# WiFi_board.net
KiCad netlist of a schematic drawn in Altium Designer
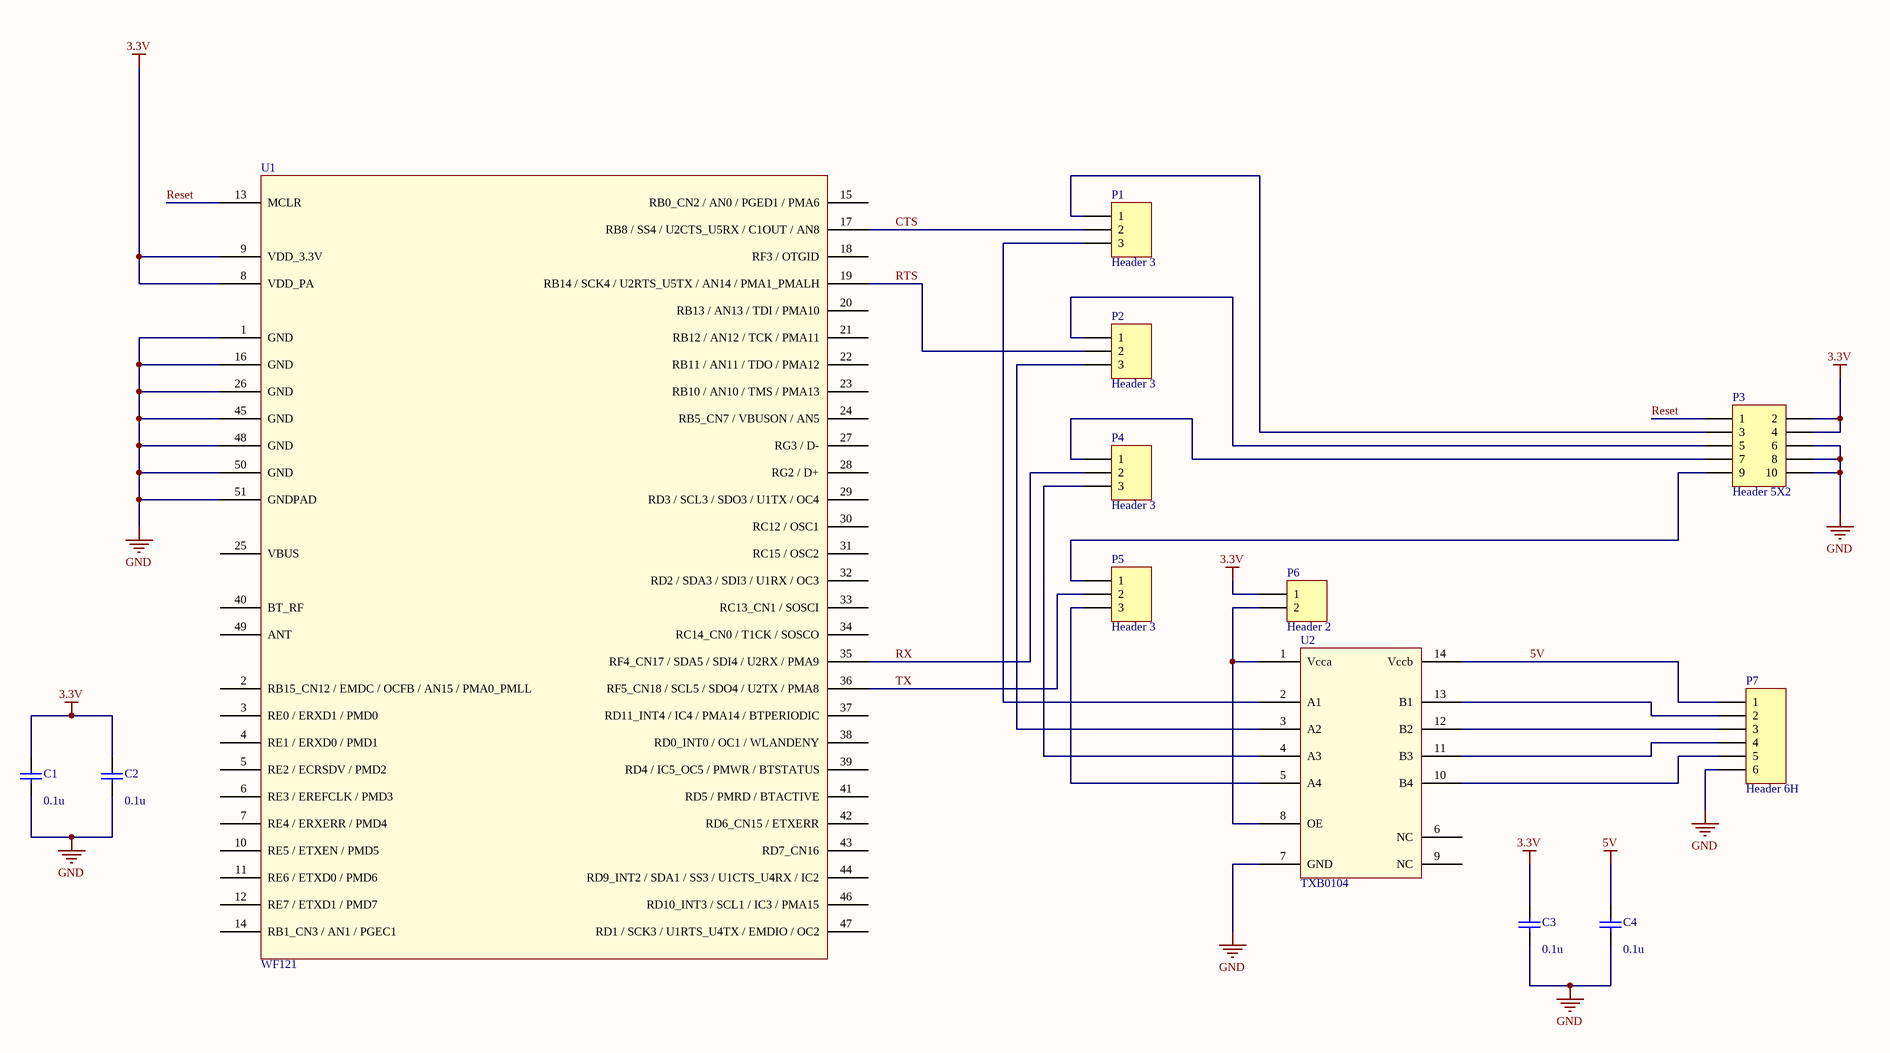
[diagram p0: WiFi_board.SchDoc]

(export (version "E")
  (design (tool "Eeschema 10.0.6"))
  (components
    (comp (ref "C1")
      (value "0.1u")
      (footprint "C1206")
      (description "Capacitor (Semiconductor SIM Model)")
      (fields (field (name "Comment") "C1") (field (name "PUBLISHER") "Altium Limited"))
      (libsource (lib "Miscellaneous Devices") (part "Cap Semi"))
    )
    (comp (ref "C2")
      (value "0.1u")
      (footprint "C1206")
      (description "Capacitor (Semiconductor SIM Model)")
      (fields (field (name "Comment") "C2") (field (name "PUBLISHER") "Altium Limited"))
      (libsource (lib "Miscellaneous Devices") (part "Cap Semi"))
    )
    (comp (ref "C3")
      (value "0.1u")
      (footprint "C1206")
      (description "Capacitor (Semiconductor SIM Model)")
      (fields (field (name "Comment") "Cap Semi") (field (name "PUBLISHER") "Altium Limited"))
      (libsource (lib "Miscellaneous Devices") (part "Cap Semi"))
    )
    (comp (ref "C4")
      (value "0.1u")
      (footprint "C1206")
      (description "Capacitor (Semiconductor SIM Model)")
      (fields (field (name "Comment") "Cap Semi") (field (name "PUBLISHER") "Altium Limited"))
      (libsource (lib "Miscellaneous Devices") (part "Cap Semi"))
    )
    (comp (ref "P1")
      (value "Header 3")
      (footprint "HDR1X3")
      (description "Header, 3-Pin")
      (fields (field (name "PUBLISHER") "Altium Limited"))
      (libsource (lib "Miscellaneous Connectors") (part "Header 3"))
    )
    (comp (ref "P2")
      (value "Header 3")
      (footprint "HDR1X3")
      (description "Header, 3-Pin")
      (fields (field (name "PUBLISHER") "Altium Limited"))
      (libsource (lib "Miscellaneous Connectors") (part "Header 3"))
    )
    (comp (ref "P3")
      (value "Header 5X2")
      (footprint "HDR2X5")
      (description "Header, 5-Pin, Dual row")
      (fields (field (name "PUBLISHER") "Altium Limited"))
      (libsource (lib "Miscellaneous Connectors") (part "Header 5X2"))
    )
    (comp (ref "P4")
      (value "Header 3")
      (footprint "HDR1X3")
      (description "Header, 3-Pin")
      (fields (field (name "PUBLISHER") "Altium Limited"))
      (libsource (lib "Miscellaneous Connectors") (part "Header 3"))
    )
    (comp (ref "P5")
      (value "Header 3")
      (footprint "HDR1X3")
      (description "Header, 3-Pin")
      (fields (field (name "PUBLISHER") "Altium Limited"))
      (libsource (lib "Miscellaneous Connectors") (part "Header 3"))
    )
    (comp (ref "P6")
      (value "Header 2")
      (footprint "HDR1X2")
      (description "Header, 2-Pin")
      (fields (field (name "PUBLISHER") "Altium Limited"))
      (libsource (lib "Miscellaneous Connectors") (part "Header 2"))
    )
    (comp (ref "P7")
      (value "Header 6H")
      (footprint "HDR1X6H")
      (description "Header, 6-Pin, Right Angle")
      (fields (field (name "PUBLISHER") "Altium Limited"))
      (libsource (lib "Miscellaneous Connectors") (part "Header 6H"))
    )
    (comp (ref "U1") (value "WF121") (footprint "WF121") (libsource (lib "QuadrupedSchLib") (part "WF121")))
    (comp (ref "U2")
      (value "TXB0104")
      (footprint "TSSOP65P640X120-14N")
      (libsource (lib "QuadrupedSchLib") (part "TXB0104"))
    )
  )
  (nets
    (net (code "1") (name "/CTS") (class "Default")
      (node (ref "P1") (pin "2") (pinfunction "2_2") (pintype "passive"))
      (node (ref "U1") (pin "17") (pinfunction "RB8_/_SS4_/_U2CTS_U5RX_/_C1OUT_/_AN8_17") (pintype "passive"))
    )
    (net (code "2") (name "/RTS") (class "Default")
      (node (ref "P2") (pin "2") (pinfunction "2_2") (pintype "passive"))
      (node (ref "U1") (pin "19") (pinfunction "RB14_/_SCK4_/_U2RTS_U5TX_/_AN14_/_PMA1_PMALH_19") (pintype "passive"))
    )
    (net (code "3") (name "/RX") (class "Default")
      (node (ref "P4") (pin "2") (pinfunction "2_2") (pintype "passive"))
      (node (ref "U1") (pin "35") (pinfunction "RF4_CN17_/_SDA5_/_SDI4_/_U2RX_/_PMA9_35") (pintype "passive"))
    )
    (net (code "4") (name "/Reset") (class "Default")
      (node (ref "P3") (pin "1") (pinfunction "1_1") (pintype "passive"))
      (node (ref "U1") (pin "13") (pinfunction "MCLR_13") (pintype "passive"))
    )
    (net (code "5") (name "/TX") (class "Default")
      (node (ref "P5") (pin "2") (pinfunction "2_2") (pintype "passive"))
      (node (ref "U1") (pin "36") (pinfunction "RF5_CN18_/_SCL5_/_SDO4_/_U2TX_/_PMA8_36") (pintype "passive"))
    )
    (net (code "6") (name "3.3V") (class "Default")
      (node (ref "C1") (pin "2") (pinfunction "2_2") (pintype "passive"))
      (node (ref "C2") (pin "2") (pinfunction "2_2") (pintype "passive"))
      (node (ref "C3") (pin "2") (pinfunction "2_2") (pintype "passive"))
      (node (ref "P3") (pin "2") (pinfunction "2_2") (pintype "passive"))
      (node (ref "P3") (pin "4") (pinfunction "4_4") (pintype "passive"))
      (node (ref "P6") (pin "1") (pinfunction "1_1") (pintype "passive"))
      (node (ref "U1") (pin "8") (pinfunction "VDD_PA_8") (pintype "power_in"))
      (node (ref "U1") (pin "9") (pinfunction "VDD_3.3V_9") (pintype "power_in"))
    )
    (net (code "7") (name "5V") (class "Default")
      (node (ref "C4") (pin "2") (pinfunction "2_2") (pintype "passive"))
      (node (ref "P7") (pin "1") (pinfunction "1_1") (pintype "passive"))
      (node (ref "U2") (pin "14") (pinfunction "Vccb_14") (pintype "passive"))
    )
    (net (code "8") (name "GND") (class "Default")
      (node (ref "C1") (pin "1") (pinfunction "1_1") (pintype "passive"))
      (node (ref "C2") (pin "1") (pinfunction "1_1") (pintype "passive"))
      (node (ref "C3") (pin "1") (pinfunction "1_1") (pintype "passive"))
      (node (ref "C4") (pin "1") (pinfunction "1_1") (pintype "passive"))
      (node (ref "P3") (pin "10") (pinfunction "10_10") (pintype "passive"))
      (node (ref "P3") (pin "6") (pinfunction "6_6") (pintype "passive"))
      (node (ref "P3") (pin "8") (pinfunction "8_8") (pintype "passive"))
      (node (ref "P7") (pin "6") (pinfunction "6_6") (pintype "passive"))
      (node (ref "U1") (pin "1") (pinfunction "GND_1") (pintype "power_in"))
      (node (ref "U1") (pin "16") (pinfunction "GND_16") (pintype "power_in"))
      (node (ref "U1") (pin "26") (pinfunction "GND_26") (pintype "power_in"))
      (node (ref "U1") (pin "45") (pinfunction "GND_45") (pintype "power_in"))
      (node (ref "U1") (pin "48") (pinfunction "GND_48") (pintype "power_in"))
      (node (ref "U1") (pin "50") (pinfunction "GND_50") (pintype "power_in"))
      (node (ref "U1") (pin "51") (pinfunction "GNDPAD_51") (pintype "power_in"))
      (node (ref "U2") (pin "7") (pinfunction "GND_7") (pintype "power_in"))
    )
    (net (code "9") (name "Net-(P1-Pad1)") (class "Default")
      (node (ref "P1") (pin "1") (pinfunction "1_1") (pintype "passive"))
      (node (ref "P3") (pin "3") (pinfunction "3_3") (pintype "passive"))
    )
    (net (code "10") (name "Net-(P2-Pad1)") (class "Default")
      (node (ref "P2") (pin "1") (pinfunction "1_1") (pintype "passive"))
      (node (ref "P3") (pin "5") (pinfunction "5_5") (pintype "passive"))
    )
    (net (code "11") (name "Net-(P3-Pad7)") (class "Default")
      (node (ref "P3") (pin "7") (pinfunction "7_7") (pintype "passive"))
      (node (ref "P4") (pin "1") (pinfunction "1_1") (pintype "passive"))
    )
    (net (code "12") (name "Net-(P3-Pad9)") (class "Default")
      (node (ref "P3") (pin "9") (pinfunction "9_9") (pintype "passive"))
      (node (ref "P5") (pin "1") (pinfunction "1_1") (pintype "passive"))
    )
    (net (code "13") (name "Net-(U2-A1)") (class "Default")
      (node (ref "P1") (pin "3") (pinfunction "3_3") (pintype "passive"))
      (node (ref "U2") (pin "2") (pinfunction "A1_2") (pintype "passive"))
    )
    (net (code "14") (name "Net-(U2-A2)") (class "Default")
      (node (ref "P2") (pin "3") (pinfunction "3_3") (pintype "passive"))
      (node (ref "U2") (pin "3") (pinfunction "A2_3") (pintype "passive"))
    )
    (net (code "15") (name "Net-(U2-A3)") (class "Default")
      (node (ref "P4") (pin "3") (pinfunction "3_3") (pintype "passive"))
      (node (ref "U2") (pin "4") (pinfunction "A3_4") (pintype "passive"))
    )
    (net (code "16") (name "Net-(U2-A4)") (class "Default")
      (node (ref "P5") (pin "3") (pinfunction "3_3") (pintype "passive"))
      (node (ref "U2") (pin "5") (pinfunction "A4_5") (pintype "passive"))
    )
    (net (code "17") (name "Net-(U2-B1)") (class "Default")
      (node (ref "P7") (pin "2") (pinfunction "2_2") (pintype "passive"))
      (node (ref "U2") (pin "13") (pinfunction "B1_13") (pintype "passive"))
    )
    (net (code "18") (name "Net-(U2-B2)") (class "Default")
      (node (ref "P7") (pin "3") (pinfunction "3_3") (pintype "passive"))
      (node (ref "U2") (pin "12") (pinfunction "B2_12") (pintype "passive"))
    )
    (net (code "19") (name "Net-(U2-B3)") (class "Default")
      (node (ref "P7") (pin "4") (pinfunction "4_4") (pintype "passive"))
      (node (ref "U2") (pin "11") (pinfunction "B3_11") (pintype "passive"))
    )
    (net (code "20") (name "Net-(U2-B4)") (class "Default")
      (node (ref "P7") (pin "5") (pinfunction "5_5") (pintype "passive"))
      (node (ref "U2") (pin "10") (pinfunction "B4_10") (pintype "passive"))
    )
    (net (code "21") (name "Net-(U2-OE)") (class "Default")
      (node (ref "P6") (pin "2") (pinfunction "2_2") (pintype "passive"))
      (node (ref "U2") (pin "1") (pinfunction "Vcca_1") (pintype "power_in"))
      (node (ref "U2") (pin "8") (pinfunction "OE_8") (pintype "passive"))
    )
    (net (code "22") (name "unconnected-(U1-ANT-Pad49)") (class "Default")
      (node (ref "U1") (pin "49") (pinfunction "ANT_49") (pintype "passive"))
    )
    (net (code "23") (name "unconnected-(U1-BT_RF-Pad40)") (class "Default")
      (node (ref "U1") (pin "40") (pinfunction "BT_RF_40") (pintype "passive"))
    )
    (net (code "24") (name "unconnected-(U1-RB0_CN2_{slash}_AN0_{slash}_PGED1_{slash}_PMA6-Pad15)") (class "Default")
      (node (ref "U1") (pin "15") (pinfunction "RB0_CN2_/_AN0_/_PGED1_/_PMA6_15") (pintype "passive"))
    )
    (net (code "25") (name "unconnected-(U1-RB1_CN3_{slash}_AN1_{slash}_PGEC1-Pad14)") (class "Default")
      (node (ref "U1") (pin "14") (pinfunction "RB1_CN3_/_AN1_/_PGEC1_14") (pintype "passive"))
    )
    (net (code "26") (name "unconnected-(U1-RB5_CN7_{slash}_VBUSON_{slash}_AN5-Pad24)") (class "Default")
      (node (ref "U1") (pin "24") (pinfunction "RB5_CN7_/_VBUSON_/_AN5_24") (pintype "passive"))
    )
    (net (code "27") (name "unconnected-(U1-RB10_{slash}_AN10_{slash}_TMS_{slash}_PMA13-Pad23)") (class "Default")
      (node (ref "U1") (pin "23") (pinfunction "RB10_/_AN10_/_TMS_/_PMA13_23") (pintype "passive"))
    )
    (net (code "28") (name "unconnected-(U1-RB11_{slash}_AN11_{slash}_TDO_{slash}_PMA12-Pad22)") (class "Default")
      (node (ref "U1") (pin "22") (pinfunction "RB11_/_AN11_/_TDO_/_PMA12_22") (pintype "passive"))
    )
    (net (code "29") (name "unconnected-(U1-RB12_{slash}_AN12_{slash}_TCK_{slash}_PMA11-Pad21)") (class "Default")
      (node (ref "U1") (pin "21") (pinfunction "RB12_/_AN12_/_TCK_/_PMA11_21") (pintype "passive"))
    )
    (net (code "30") (name "unconnected-(U1-RB13_{slash}_AN13_{slash}_TDI_{slash}_PMA10-Pad20)") (class "Default")
      (node (ref "U1") (pin "20") (pinfunction "RB13_/_AN13_/_TDI_/_PMA10_20") (pintype "passive"))
    )
    (net (code "31") (name "unconnected-(U1-RB15_CN12_{slash}_EMDC_{slash}_OCFB_{slash}_AN15_{slash}_PMA0_PMLL-Pad2)") (class "Default")
      (node (ref "U1") (pin "2") (pinfunction "RB15_CN12_/_EMDC_/_OCFB_/_AN15_/_PMA0_PMLL_2") (pintype "passive"))
    )
    (net (code "32") (name "unconnected-(U1-RC12_{slash}_OSC1-Pad30)") (class "Default")
      (node (ref "U1") (pin "30") (pinfunction "RC12_/_OSC1_30") (pintype "passive"))
    )
    (net (code "33") (name "unconnected-(U1-RC13_CN1_{slash}_SOSCI-Pad33)") (class "Default")
      (node (ref "U1") (pin "33") (pinfunction "RC13_CN1_/_SOSCI_33") (pintype "passive"))
    )
    (net (code "34") (name "unconnected-(U1-RC14_CN0_{slash}_T1CK_{slash}_SOSCO-Pad34)") (class "Default")
      (node (ref "U1") (pin "34") (pinfunction "RC14_CN0_/_T1CK_/_SOSCO_34") (pintype "passive"))
    )
    (net (code "35") (name "unconnected-(U1-RC15_{slash}_OSC2-Pad31)") (class "Default")
      (node (ref "U1") (pin "31") (pinfunction "RC15_/_OSC2_31") (pintype "passive"))
    )
    (net (code "36") (name "unconnected-(U1-RD0_INT0_{slash}_OC1_{slash}_WLANDENY-Pad38)") (class "Default")
      (node (ref "U1") (pin "38") (pinfunction "RD0_INT0_/_OC1_/_WLANDENY_38") (pintype "passive"))
    )
    (net (code "37") (name "unconnected-(U1-RD1_{slash}_SCK3_{slash}_U1RTS_U4TX_{slash}_EMDIO_{slash}_OC2-Pad47)") (class "Default")
      (node (ref "U1") (pin "47") (pinfunction "RD1_/_SCK3_/_U1RTS_U4TX_/_EMDIO_/_OC2_47") (pintype "passive"))
    )
    (net (code "38") (name "unconnected-(U1-RD2_{slash}_SDA3_{slash}_SDI3_{slash}_U1RX_{slash}_OC3-Pad32)") (class "Default")
      (node (ref "U1") (pin "32") (pinfunction "RD2_/_SDA3_/_SDI3_/_U1RX_/_OC3_32") (pintype "passive"))
    )
    (net (code "39") (name "unconnected-(U1-RD3_{slash}_SCL3_{slash}_SDO3_{slash}_U1TX_{slash}_OC4-Pad29)") (class "Default")
      (node (ref "U1") (pin "29") (pinfunction "RD3_/_SCL3_/_SDO3_/_U1TX_/_OC4_29") (pintype "passive"))
    )
    (net (code "40") (name "unconnected-(U1-RD4_{slash}_IC5_OC5_{slash}_PMWR_{slash}_BTSTATUS-Pad39)") (class "Default")
      (node (ref "U1") (pin "39") (pinfunction "RD4_/_IC5_OC5_/_PMWR_/_BTSTATUS_39") (pintype "passive"))
    )
    (net (code "41") (name "unconnected-(U1-RD5_{slash}_PMRD_{slash}_BTACTIVE-Pad41)") (class "Default")
      (node (ref "U1") (pin "41") (pinfunction "RD5_/_PMRD_/_BTACTIVE_41") (pintype "passive"))
    )
    (net (code "42") (name "unconnected-(U1-RD6_CN15_{slash}_ETXERR-Pad42)") (class "Default")
      (node (ref "U1") (pin "42") (pinfunction "RD6_CN15_/_ETXERR_42") (pintype "passive"))
    )
    (net (code "43") (name "unconnected-(U1-RD7_CN16-Pad43)") (class "Default")
      (node (ref "U1") (pin "43") (pinfunction "RD7_CN16_43") (pintype "passive"))
    )
    (net (code "44") (name "unconnected-(U1-RD9_INT2_{slash}_SDA1_{slash}_SS3_{slash}_U1CTS_U4RX_{slash}_IC2-Pad44)") (class "Default")
      (node (ref "U1") (pin "44") (pinfunction "RD9_INT2_/_SDA1_/_SS3_/_U1CTS_U4RX_/_IC2_44") (pintype "passive"))
    )
    (net (code "45") (name "unconnected-(U1-RD10_INT3_{slash}_SCL1_{slash}_IC3_{slash}_PMA15-Pad46)") (class "Default")
      (node (ref "U1") (pin "46") (pinfunction "RD10_INT3_/_SCL1_/_IC3_/_PMA15_46") (pintype "passive"))
    )
    (net (code "46") (name "unconnected-(U1-RD11_INT4_{slash}_IC4_{slash}_PMA14_{slash}_BTPERIODIC-Pad37)") (class "Default")
      (node (ref "U1") (pin "37") (pinfunction "RD11_INT4_/_IC4_/_PMA14_/_BTPERIODIC_37") (pintype "passive"))
    )
    (net (code "47") (name "unconnected-(U1-RE0_{slash}_ERXD1_{slash}_PMD0-Pad3)") (class "Default")
      (node (ref "U1") (pin "3") (pinfunction "RE0_/_ERXD1_/_PMD0_3") (pintype "passive"))
    )
    (net (code "48") (name "unconnected-(U1-RE1_{slash}_ERXD0_{slash}_PMD1-Pad4)") (class "Default")
      (node (ref "U1") (pin "4") (pinfunction "RE1_/_ERXD0_/_PMD1_4") (pintype "passive"))
    )
    (net (code "49") (name "unconnected-(U1-RE2_{slash}_ECRSDV_{slash}_PMD2-Pad5)") (class "Default")
      (node (ref "U1") (pin "5") (pinfunction "RE2_/_ECRSDV_/_PMD2_5") (pintype "passive"))
    )
    (net (code "50") (name "unconnected-(U1-RE3_{slash}_EREFCLK_{slash}_PMD3-Pad6)") (class "Default")
      (node (ref "U1") (pin "6") (pinfunction "RE3_/_EREFCLK_/_PMD3_6") (pintype "passive"))
    )
    (net (code "51") (name "unconnected-(U1-RE4_{slash}_ERXERR_{slash}_PMD4-Pad7)") (class "Default")
      (node (ref "U1") (pin "7") (pinfunction "RE4_/_ERXERR_/_PMD4_7") (pintype "passive"))
    )
    (net (code "52") (name "unconnected-(U1-RE5_{slash}_ETXEN_{slash}_PMD5-Pad10)") (class "Default")
      (node (ref "U1") (pin "10") (pinfunction "RE5_/_ETXEN_/_PMD5_10") (pintype "passive"))
    )
    (net (code "53") (name "unconnected-(U1-RE6_{slash}_ETXD0_{slash}_PMD6-Pad11)") (class "Default")
      (node (ref "U1") (pin "11") (pinfunction "RE6_/_ETXD0_/_PMD6_11") (pintype "passive"))
    )
    (net (code "54") (name "unconnected-(U1-RE7_{slash}_ETXD1_{slash}_PMD7-Pad12)") (class "Default")
      (node (ref "U1") (pin "12") (pinfunction "RE7_/_ETXD1_/_PMD7_12") (pintype "passive"))
    )
    (net (code "55") (name "unconnected-(U1-RF3_{slash}_OTGID-Pad18)") (class "Default")
      (node (ref "U1") (pin "18") (pinfunction "RF3_/_OTGID_18") (pintype "passive"))
    )
    (net (code "56") (name "unconnected-(U1-RG2_{slash}_D+-Pad28)") (class "Default")
      (node (ref "U1") (pin "28") (pinfunction "RG2_/_D+_28") (pintype "passive"))
    )
    (net (code "57") (name "unconnected-(U1-RG3_{slash}_D--Pad27)") (class "Default")
      (node (ref "U1") (pin "27") (pinfunction "RG3_/_D-_27") (pintype "passive"))
    )
    (net (code "58") (name "unconnected-(U1-VBUS-Pad25)") (class "Default")
      (node (ref "U1") (pin "25") (pinfunction "VBUS_25") (pintype "power_in"))
    )
    (net (code "59") (name "unconnected-(U2-NC-Pad6)") (class "Default")
      (node (ref "U2") (pin "6") (pinfunction "NC_6") (pintype "passive"))
    )
    (net (code "60") (name "unconnected-(U2-NC-Pad9)") (class "Default")
      (node (ref "U2") (pin "9") (pinfunction "NC_9") (pintype "passive"))
    )
  )
)
